# minipov.net
KiCad netlist of a schematic drawn in EAGLE
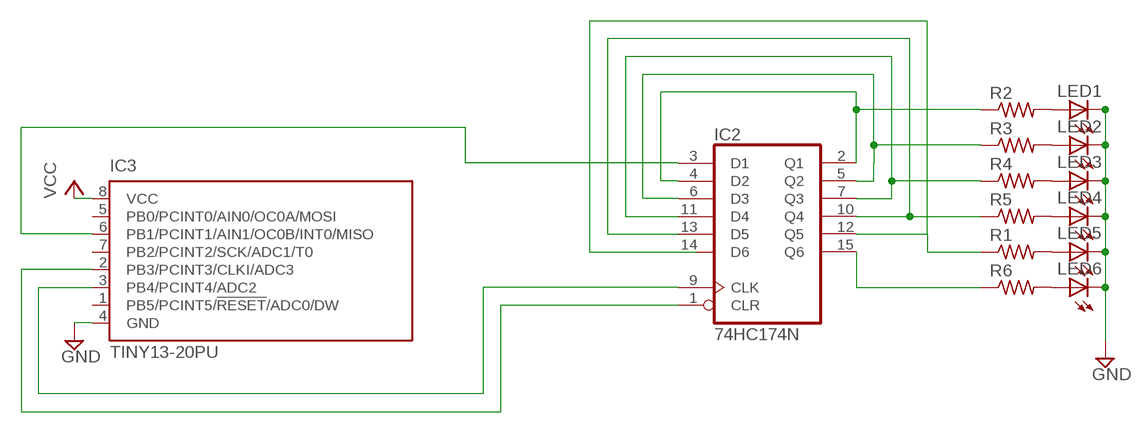
[diagram p0: schematic, sheet 1]

(export (version "E")
  (design (tool "Eeschema 10.0.6"))
  (components
    (comp (ref "IC2")
      (value "74HC174N")
      (footprint "eagle-import:DIL16")
      (libsource (lib "eagle-import") (part "74174NHC"))
    )
    (comp (ref "IC3")
      (value "TINY13-20PU")
      (footprint "eagle-import:DIL08")
      (fields (field (name "MPN") "ATTINY13-20PU"))
      (libsource (lib "eagle-import") (part "TINY13PU-20"))
    )
    (comp (ref "LED1")
      (value "LED10MM")
      (footprint "eagle-import:LED10MM")
      (libsource (lib "eagle-import") (part "LED10MM"))
    )
    (comp (ref "LED2")
      (value "LED10MM")
      (footprint "eagle-import:LED10MM")
      (libsource (lib "eagle-import") (part "LED10MM"))
    )
    (comp (ref "LED3")
      (value "LED10MM")
      (footprint "eagle-import:LED10MM")
      (libsource (lib "eagle-import") (part "LED10MM"))
    )
    (comp (ref "LED4")
      (value "LED10MM")
      (footprint "eagle-import:LED10MM")
      (libsource (lib "eagle-import") (part "LED10MM"))
    )
    (comp (ref "LED5")
      (value "LED10MM")
      (footprint "eagle-import:LED10MM")
      (libsource (lib "eagle-import") (part "LED10MM"))
    )
    (comp (ref "LED6")
      (value "LED10MM")
      (footprint "eagle-import:LED10MM")
      (libsource (lib "eagle-import") (part "LED10MM"))
    )
    (comp (ref "R1")
      (value "R-US_0207/5V")
      (footprint "eagle-import:0207_5V")
      (libsource (lib "eagle-import") (part "R-US_0207/5V"))
    )
    (comp (ref "R2")
      (value "R-US_0207/5V")
      (footprint "eagle-import:0207_5V")
      (libsource (lib "eagle-import") (part "R-US_0207/5V"))
    )
    (comp (ref "R3")
      (value "R-US_0207/5V")
      (footprint "eagle-import:0207_5V")
      (libsource (lib "eagle-import") (part "R-US_0207/5V"))
    )
    (comp (ref "R4")
      (value "R-US_0207/5V")
      (footprint "eagle-import:0207_5V")
      (libsource (lib "eagle-import") (part "R-US_0207/5V"))
    )
    (comp (ref "R5")
      (value "R-US_0207/5V")
      (footprint "eagle-import:0207_5V")
      (libsource (lib "eagle-import") (part "R-US_0207/5V"))
    )
    (comp (ref "R6")
      (value "R-US_0207/5V")
      (footprint "eagle-import:0207_5V")
      (libsource (lib "eagle-import") (part "R-US_0207/5V"))
    )
  )
  (nets
    (net (code "1") (name "GND") (class "Default")
      (node (ref "IC3") (pin "4") (pinfunction "GND_4") (pintype "power_in"))
      (node (ref "LED1") (pin "K") (pinfunction "C_K") (pintype "passive"))
      (node (ref "LED2") (pin "K") (pinfunction "C_K") (pintype "passive"))
      (node (ref "LED3") (pin "K") (pinfunction "C_K") (pintype "passive"))
      (node (ref "LED4") (pin "K") (pinfunction "C_K") (pintype "passive"))
      (node (ref "LED5") (pin "K") (pinfunction "C_K") (pintype "passive"))
      (node (ref "LED6") (pin "K") (pinfunction "C_K") (pintype "passive"))
    )
    (net (code "2") (name "Net-(IC2A-CLK)") (class "Default")
      (node (ref "IC2") (pin "9") (pinfunction "CLK_9") (pintype "input"))
      (node (ref "IC3") (pin "3") (pinfunction "PB4/PCINT4/ADC2_3") (pintype "bidirectional"))
    )
    (net (code "3") (name "Net-(IC2A-CLR)") (class "Default")
      (node (ref "IC2") (pin "1") (pinfunction "CLR_1") (pintype "input"))
      (node (ref "IC3") (pin "2") (pinfunction "PB3/PCINT3/CLKI/ADC3_2") (pintype "bidirectional"))
    )
    (net (code "4") (name "Net-(IC2A-D1)") (class "Default")
      (node (ref "IC2") (pin "3") (pinfunction "D1_3") (pintype "input"))
      (node (ref "IC3") (pin "6") (pinfunction "PB1/PCINT1/AIN1/OC0B/INT0/MISO_6") (pintype "bidirectional"))
    )
    (net (code "5") (name "Net-(IC2A-D2)") (class "Default")
      (node (ref "IC2") (pin "2") (pinfunction "Q1_2") (pintype "output"))
      (node (ref "IC2") (pin "4") (pinfunction "D2_4") (pintype "input"))
      (node (ref "R2") (pin "1") (pinfunction "1_1") (pintype "passive"))
    )
    (net (code "6") (name "Net-(IC2A-D3)") (class "Default")
      (node (ref "IC2") (pin "5") (pinfunction "Q2_5") (pintype "output"))
      (node (ref "IC2") (pin "6") (pinfunction "D3_6") (pintype "input"))
      (node (ref "R3") (pin "1") (pinfunction "1_1") (pintype "passive"))
    )
    (net (code "7") (name "Net-(IC2A-D4)") (class "Default")
      (node (ref "IC2") (pin "11") (pinfunction "D4_11") (pintype "input"))
      (node (ref "IC2") (pin "7") (pinfunction "Q3_7") (pintype "output"))
      (node (ref "R4") (pin "1") (pinfunction "1_1") (pintype "passive"))
    )
    (net (code "8") (name "Net-(IC2A-D5)") (class "Default")
      (node (ref "IC2") (pin "10") (pinfunction "Q4_10") (pintype "output"))
      (node (ref "IC2") (pin "13") (pinfunction "D5_13") (pintype "input"))
      (node (ref "R5") (pin "1") (pinfunction "1_1") (pintype "passive"))
    )
    (net (code "9") (name "Net-(IC2A-Q5)") (class "Default")
      (node (ref "IC2") (pin "12") (pinfunction "Q5_12") (pintype "output"))
      (node (ref "R1") (pin "1") (pinfunction "1_1") (pintype "passive"))
    )
    (net (code "10") (name "Net-(IC2A-Q6)") (class "Default")
      (node (ref "IC2") (pin "15") (pinfunction "Q6_15") (pintype "output"))
      (node (ref "R6") (pin "1") (pinfunction "1_1") (pintype "passive"))
    )
    (net (code "11") (name "Net-(LED1-PadA)") (class "Default")
      (node (ref "LED1") (pin "A") (pinfunction "A_A") (pintype "passive"))
      (node (ref "R2") (pin "2") (pinfunction "2_2") (pintype "passive"))
    )
    (net (code "12") (name "Net-(LED2-PadA)") (class "Default")
      (node (ref "LED2") (pin "A") (pinfunction "A_A") (pintype "passive"))
      (node (ref "R3") (pin "2") (pinfunction "2_2") (pintype "passive"))
    )
    (net (code "13") (name "Net-(LED3-PadA)") (class "Default")
      (node (ref "LED3") (pin "A") (pinfunction "A_A") (pintype "passive"))
      (node (ref "R4") (pin "2") (pinfunction "2_2") (pintype "passive"))
    )
    (net (code "14") (name "Net-(LED4-PadA)") (class "Default")
      (node (ref "LED4") (pin "A") (pinfunction "A_A") (pintype "passive"))
      (node (ref "R5") (pin "2") (pinfunction "2_2") (pintype "passive"))
    )
    (net (code "15") (name "Net-(LED5-PadA)") (class "Default")
      (node (ref "LED5") (pin "A") (pinfunction "A_A") (pintype "passive"))
      (node (ref "R1") (pin "2") (pinfunction "2_2") (pintype "passive"))
    )
    (net (code "16") (name "Net-(LED6-PadA)") (class "Default")
      (node (ref "LED6") (pin "A") (pinfunction "A_A") (pintype "passive"))
      (node (ref "R6") (pin "2") (pinfunction "2_2") (pintype "passive"))
    )
    (net (code "17") (name "VCC") (class "Default")
      (node (ref "IC3") (pin "8") (pinfunction "VCC_8") (pintype "power_in"))
    )
    (net (code "18") (name "unconnected-(IC2A-D6-Pad14)") (class "Default")
      (node (ref "IC2") (pin "14") (pinfunction "D6_14") (pintype "input"))
    )
    (net (code "19") (name "unconnected-(IC3-PB0{slash}PCINT0{slash}AIN0{slash}OC0A{slash}MOSI-Pad5)") (class "Default")
      (node (ref "IC3") (pin "5") (pinfunction "PB0/PCINT0/AIN0/OC0A/MOSI_5") (pintype "bidirectional"))
    )
    (net (code "20") (name "unconnected-(IC3-PB2{slash}PCINT2{slash}SCK{slash}ADC1{slash}T0-Pad7)") (class "Default")
      (node (ref "IC3") (pin "7") (pinfunction "PB2/PCINT2/SCK/ADC1/T0_7") (pintype "bidirectional"))
    )
    (net (code "21") (name "unconnected-(IC3-PB5{slash}PCINT5{slash}~{RESET}{slash}ADC0{slash}DW-Pad1)") (class "Default")
      (node (ref "IC3") (pin "1") (pinfunction "PB5/PCINT5/~{RESET}/ADC0/DW_1") (pintype "bidirectional"))
    )
  )
)
